# 12-UWB-Power.net
KiCad netlist of a schematic drawn in Altium Designer
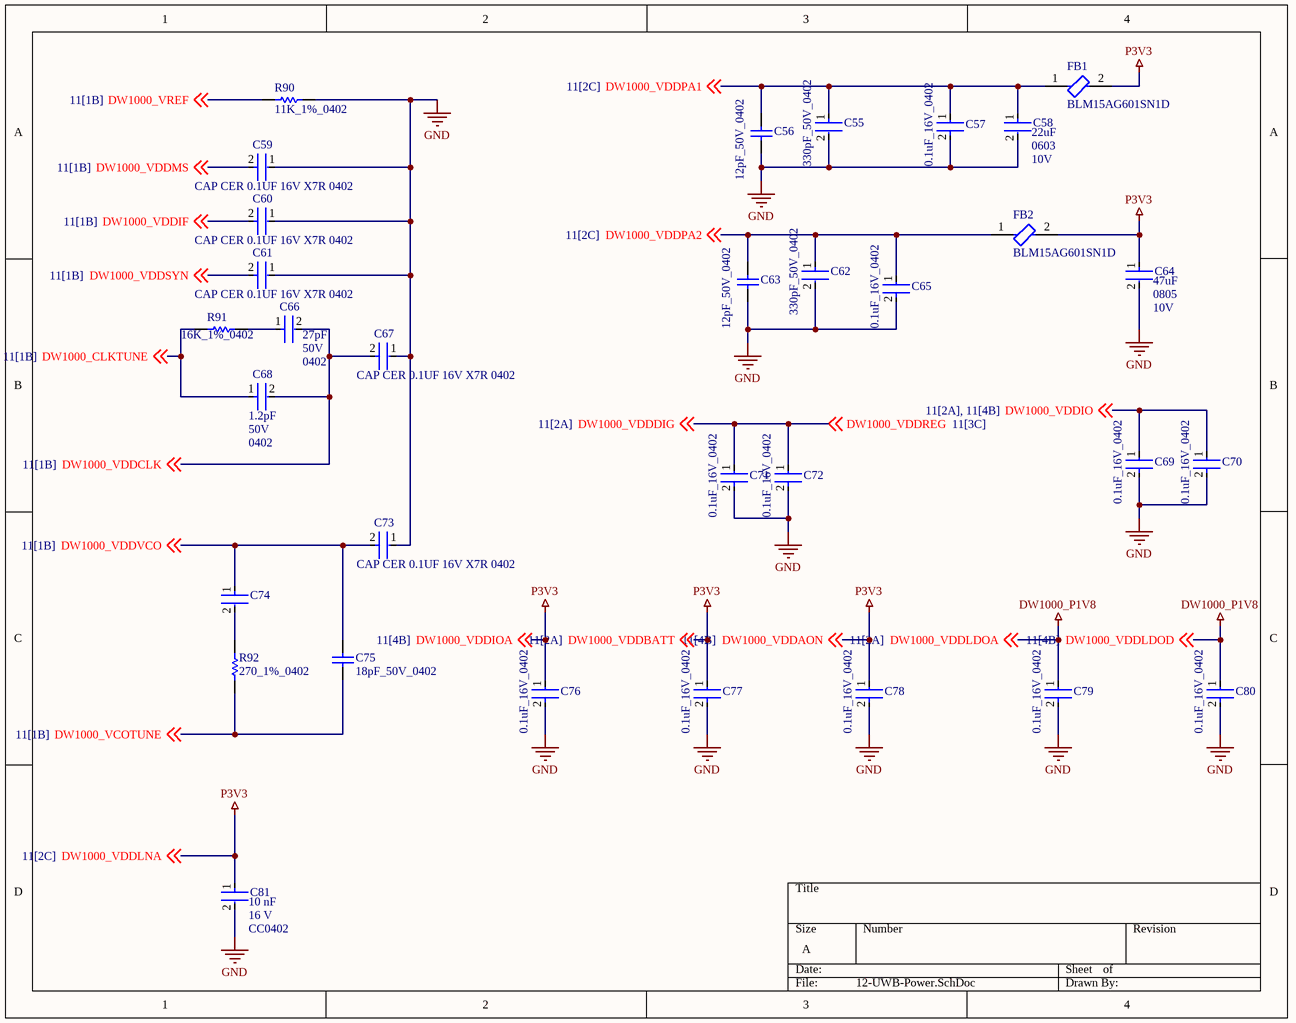
[diagram p0: 12-UWB-Power.SchDoc]

(export (version "E")
  (design (tool "Eeschema 10.0.6"))
  (components
    (comp (ref "C55")
      (value "330pF_50V_0402")
      (footprint "FP-GRM155-0_05-MFG")
      (description "Chip Multilayer Ceramic Capacitors for General Purpose, 0402, 330pF, C0G, 30ppm/°C, 5%, 50V")
      (fields (field (name "TOLERANCE") "5%") (field (name "VOLTAGE") "50V"))
      (libsource (lib "Altium Content Vault") (part "02cd4be3c70576c341d710602a673aa"))
    )
    (comp (ref "C56")
      (value "12pF_50V_0402")
      (footprint "CAPC1005X55X25LL05T05")
      (description "Chip Capacitor, 12 pF, +/- 5%, 50 V, -55 to 125 degC, 0402 (1005 Metric), RoHS, Tape and Reel")
      (fields (field (name "MANUFACTURER") "Yageo") (field (name "TOLERANCE") "±5%"))
      (libsource (lib "Altium Content Vault") (part "CAP-NP-2"))
    )
    (comp (ref "C57")
      (value "0.1uF_16V_0402")
      (footprint "FP-GRM15-MFG")
      (fields
        (field (name "MANUFACTURER PART NUMBER") "GRM155R71C104KA88D")
        (field (name "TOLERANCE") "10%")
        (field (name "OCTOPART") "https://octopart.com/grm155r71c104ka88d-murata-196880")
      )
      (libsource (lib "Altium Content Vault") (part "236180d848d6139a670b325ea6854c9"))
    )
    (comp (ref "C58")
      (value "GRM188R61A226ME15D")
      (footprint "FP-GRM188-0_2-IPC_C")
      (description "Chip Multilayer Ceramic Capacitors for General Purpose, 0603, 22uF, X5R, 15%, 20%, 10V")
      (fields
        (field (name "TOLERANCE") "20%")
        (field (name "CAPACITANCE") "22uF")
        (field (name "VOLTAGE RATING") "10V")
        (field (name "CASE CODE (IMPERIAL)") "0603")
      )
      (libsource (lib "Altium Content Vault") (part "11868f565c42a9108669ba33697ecf6"))
    )
    (comp (ref "C59")
      (value "GRM155R71C104KA88D")
      (footprint "FP-GRM15-MFG")
      (description "CAP CER 0.1UF 16V X7R 0402")
      (fields
        (field (name "TOLERANCE") "10%")
        (field (name "OCTOPART") "https://octopart.com/grm155r71c104ka88d-murata-196880")
        (field (name "DIGIKEY DESCRIPTION") "CAP CER 0.1UF 16V X7R 0402")
      )
      (libsource (lib "Altium Content Vault") (part "236180d848d6139a670b325ea6854c9"))
    )
    (comp (ref "C60")
      (value "GRM155R71C104KA88D")
      (footprint "FP-GRM15-MFG")
      (description "CAP CER 0.1UF 16V X7R 0402")
      (fields
        (field (name "TOLERANCE") "10%")
        (field (name "OCTOPART") "https://octopart.com/grm155r71c104ka88d-murata-196880")
        (field (name "DIGIKEY DESCRIPTION") "CAP CER 0.1UF 16V X7R 0402")
      )
      (libsource (lib "Altium Content Vault") (part "236180d848d6139a670b325ea6854c9"))
    )
    (comp (ref "C61")
      (value "GRM155R71C104KA88D")
      (footprint "FP-GRM15-MFG")
      (description "CAP CER 0.1UF 16V X7R 0402")
      (fields
        (field (name "TOLERANCE") "10%")
        (field (name "OCTOPART") "https://octopart.com/grm155r71c104ka88d-murata-196880")
        (field (name "DIGIKEY DESCRIPTION") "CAP CER 0.1UF 16V X7R 0402")
      )
      (libsource (lib "Altium Content Vault") (part "236180d848d6139a670b325ea6854c9"))
    )
    (comp (ref "C62")
      (value "330pF_50V_0402")
      (footprint "FP-GRM155-0_05-MFG")
      (description "Chip Multilayer Ceramic Capacitors for General Purpose, 0402, 330pF, C0G, 30ppm/°C, 5%, 50V")
      (fields (field (name "TOLERANCE") "5%") (field (name "VOLTAGE") "50V"))
      (libsource (lib "Altium Content Vault") (part "02cd4be3c70576c341d710602a673aa"))
    )
    (comp (ref "C63")
      (value "12pF_50V_0402")
      (footprint "CAPC1005X55X25LL05T05")
      (description "Chip Capacitor, 12 pF, +/- 5%, 50 V, -55 to 125 degC, 0402 (1005 Metric), RoHS, Tape and Reel")
      (fields (field (name "MANUFACTURER") "Yageo") (field (name "TOLERANCE") "±5%"))
      (libsource (lib "Altium Content Vault") (part "CAP-NP-2"))
    )
    (comp (ref "C64")
      (value "GRM21BR61A476ME15L")
      (footprint "FP-GRM21B-0_2-e0_2_0_7-IPC_A")
      (description "Chip Multilayer Ceramic Capacitors for General Purpose, 0805, 47uF, X5R, 15%, 20%, 10V")
      (fields
        (field (name "CAPACITANCE") "47uF")
        (field (name "TOLERANCE") "20%")
        (field (name "CASE CODE (IMPERIAL)") "0805")
        (field (name "VOLTAGE") "10V")
      )
      (libsource (lib "Altium Content Vault") (part "b4654b650e69147ec39a6b967a45e02"))
    )
    (comp (ref "C65")
      (value "0.1uF_16V_0402")
      (footprint "FP-GRM15-MFG")
      (fields
        (field (name "MANUFACTURER PART NUMBER") "GRM155R71C104KA88D")
        (field (name "TOLERANCE") "10%")
        (field (name "OCTOPART") "https://octopart.com/grm155r71c104ka88d-murata-196880")
      )
      (libsource (lib "Altium Content Vault") (part "236180d848d6139a670b325ea6854c9"))
    )
    (comp (ref "C66")
      (value "04025A270JAT2A")
      (footprint "FP-0402-L_1_0_1-W_0_5_0_1-MFG")
      (description "General Purpose Ceramic Capacitor, 0402, 27pF, 5%, C0G, 30ppm/°C, 50V")
      (fields
        (field (name "VOLTAGE RATING") "50V")
        (field (name "VOLTAGE") "50V")
        (field (name "CASE/PACKAGE") "0402")
        (field (name "TOLERANCE") "5%")
        (field (name "CAPACITANCE") "27pF")
      )
      (libsource (lib "Altium Content Vault") (part "b4654b650e69147ec39a6b967a45e02"))
    )
    (comp (ref "C67")
      (value "GRM155R71C104KA88D")
      (footprint "FP-GRM15-MFG")
      (description "CAP CER 0.1UF 16V X7R 0402")
      (fields
        (field (name "TOLERANCE") "10%")
        (field (name "OCTOPART") "https://octopart.com/grm155r71c104ka88d-murata-196880")
        (field (name "DIGIKEY DESCRIPTION") "CAP CER 0.1UF 16V X7R 0402")
      )
      (libsource (lib "Altium Content Vault") (part "236180d848d6139a670b325ea6854c9"))
    )
    (comp (ref "C68")
      (value "GJM1555C1H1R2BB01D")
      (footprint "FP-GJM155-0_05-IPC_B")
      (description "Multi-Layer Ceramic Capacitor 1.2pF C0G  ±0.1pF 0402 Paper T/R")
      (fields
        (field (name "VOLTAGE RATING (DC)") "50V")
        (field (name "CASE CODE (IMPERIAL)") "0402")
        (field (name "VOLTAGE") "50V")
        (field (name "CAPACITANCE") "1.2pF")
      )
      (libsource (lib "Altium Content Vault") (part "02cd4be3c70576c341d710602a673aa"))
    )
    (comp (ref "C69")
      (value "0.1uF_16V_0402")
      (footprint "FP-GRM15-MFG")
      (fields
        (field (name "MANUFACTURER PART NUMBER") "GRM155R71C104KA88D")
        (field (name "TOLERANCE") "10%")
        (field (name "OCTOPART") "https://octopart.com/grm155r71c104ka88d-murata-196880")
      )
      (libsource (lib "Altium Content Vault") (part "236180d848d6139a670b325ea6854c9"))
    )
    (comp (ref "C70")
      (value "0.1uF_16V_0402")
      (footprint "FP-GRM15-MFG")
      (fields
        (field (name "MANUFACTURER PART NUMBER") "GRM155R71C104KA88D")
        (field (name "TOLERANCE") "10%")
        (field (name "OCTOPART") "https://octopart.com/grm155r71c104ka88d-murata-196880")
      )
      (libsource (lib "Altium Content Vault") (part "236180d848d6139a670b325ea6854c9"))
    )
    (comp (ref "C71")
      (value "0.1uF_16V_0402")
      (footprint "FP-GRM15-MFG")
      (fields
        (field (name "MANUFACTURER PART NUMBER") "GRM155R71C104KA88D")
        (field (name "TOLERANCE") "10%")
        (field (name "OCTOPART") "https://octopart.com/grm155r71c104ka88d-murata-196880")
      )
      (libsource (lib "Altium Content Vault") (part "236180d848d6139a670b325ea6854c9"))
    )
    (comp (ref "C72")
      (value "0.1uF_16V_0402")
      (footprint "FP-GRM15-MFG")
      (fields
        (field (name "MANUFACTURER PART NUMBER") "GRM155R71C104KA88D")
        (field (name "TOLERANCE") "10%")
        (field (name "OCTOPART") "https://octopart.com/grm155r71c104ka88d-murata-196880")
      )
      (libsource (lib "Altium Content Vault") (part "236180d848d6139a670b325ea6854c9"))
    )
    (comp (ref "C73")
      (value "GRM155R71C104KA88D")
      (footprint "FP-GRM15-MFG")
      (description "CAP CER 0.1UF 16V X7R 0402")
      (fields
        (field (name "TOLERANCE") "10%")
        (field (name "OCTOPART") "https://octopart.com/grm155r71c104ka88d-murata-196880")
        (field (name "DIGIKEY DESCRIPTION") "CAP CER 0.1UF 16V X7R 0402")
      )
      (libsource (lib "Altium Content Vault") (part "236180d848d6139a670b325ea6854c9"))
    )
    (comp (ref "C74")
      (value "C0402C821K5RACTU")
      (footprint "FP-C0402-BB-MFG")
      (description "CAP CER 820PF 50V 10% X7R 0402")
      (fields (field (name "TOLERANCE") "0.1") (field (name "MANUFACTURER") "Kemet"))
      (libsource (lib "Altium Content Vault") (part "b4654b650e69147ec39a6b967a45e02"))
    )
    (comp (ref "C75")
      (value "18pF_50V_0402")
      (footprint "CAPC1005X55X25NL05T10")
      (fields (field (name "PART NUMBER") "GRM1555C1H180JA01D") (field (name "MANUFACTURER") "Murata"))
      (libsource (lib "Altium Content Vault") (part "CAP"))
    )
    (comp (ref "C76")
      (value "0.1uF_16V_0402")
      (footprint "FP-GRM15-MFG")
      (fields
        (field (name "MANUFACTURER PART NUMBER") "GRM155R71C104KA88D")
        (field (name "TOLERANCE") "10%")
        (field (name "OCTOPART") "https://octopart.com/grm155r71c104ka88d-murata-196880")
      )
      (libsource (lib "Altium Content Vault") (part "236180d848d6139a670b325ea6854c9"))
    )
    (comp (ref "C77")
      (value "0.1uF_16V_0402")
      (footprint "FP-GRM15-MFG")
      (fields
        (field (name "MANUFACTURER PART NUMBER") "GRM155R71C104KA88D")
        (field (name "TOLERANCE") "10%")
        (field (name "OCTOPART") "https://octopart.com/grm155r71c104ka88d-murata-196880")
      )
      (libsource (lib "Altium Content Vault") (part "236180d848d6139a670b325ea6854c9"))
    )
    (comp (ref "C78")
      (value "0.1uF_16V_0402")
      (footprint "FP-GRM15-MFG")
      (fields
        (field (name "MANUFACTURER PART NUMBER") "GRM155R71C104KA88D")
        (field (name "TOLERANCE") "10%")
        (field (name "OCTOPART") "https://octopart.com/grm155r71c104ka88d-murata-196880")
      )
      (libsource (lib "Altium Content Vault") (part "236180d848d6139a670b325ea6854c9"))
    )
    (comp (ref "C79")
      (value "0.1uF_16V_0402")
      (footprint "FP-GRM15-MFG")
      (fields
        (field (name "MANUFACTURER PART NUMBER") "GRM155R71C104KA88D")
        (field (name "TOLERANCE") "10%")
        (field (name "OCTOPART") "https://octopart.com/grm155r71c104ka88d-murata-196880")
      )
      (libsource (lib "Altium Content Vault") (part "236180d848d6139a670b325ea6854c9"))
    )
    (comp (ref "C80")
      (value "0.1uF_16V_0402")
      (footprint "FP-GRM15-MFG")
      (fields
        (field (name "MANUFACTURER PART NUMBER") "GRM155R71C104KA88D")
        (field (name "TOLERANCE") "10%")
        (field (name "OCTOPART") "https://octopart.com/grm155r71c104ka88d-murata-196880")
      )
      (libsource (lib "Altium Content Vault") (part "236180d848d6139a670b325ea6854c9"))
    )
    (comp (ref "C81")
      (value "10 nF")
      (footprint "FP-CC0402-MFG")
      (description "CAP CER 10000PF 16V X7R 0402")
      (fields
        (field (name "MANUFACTURER PART NUMBER") "CC0402KRX7R7BB103")
        (field (name "TOLERANCE") "0.1")
        (field (name "PACKAGE") "CC0402")
        (field (name "VOLTAGE RATING") "16 V")
      )
      (libsource (lib "Altium Content Vault") (part "11868f565c42a9108669ba33697ecf6"))
    )
    (comp (ref "FB1")
      (value "BLM15AG601SN1D")
      (footprint "FP-BLM15-0_05-MFG")
      (description "Chip Ferrite Bead, 0402, 600Ω @ 100MHz, 0.52Ω, 25%, 300mA")
      (fields (field (name "TOLERANCE") "25%"))
      (libsource (lib "Altium Content Vault") (part "5f30dd21d616792df468990f7003faa"))
    )
    (comp (ref "FB2")
      (value "BLM15AG601SN1D")
      (footprint "FP-BLM15-0_05-MFG")
      (description "Chip Ferrite Bead, 0402, 600Ω @ 100MHz, 0.52Ω, 25%, 300mA")
      (fields (field (name "TOLERANCE") "25%"))
      (libsource (lib "Altium Content Vault") (part "5f30dd21d616792df468990f7003faa"))
    )
    (comp (ref "R90")
      (value "11K_1%_0402")
      (footprint "RESC1005X40X25LL05T10")
      (fields (field (name "MANUFACTURER") "Yageo / Phycomp") (field (name "PART NUMBER") "RC0402FR-0711KL"))
      (libsource (lib "Altium Content Vault") (part "RES"))
    )
    (comp (ref "R91")
      (value "16K_1%_0402")
      (footprint "RESC1005X40X25ML05T10")
      (fields (field (name "MANUFACTURER") "Yageo / Phycomp") (field (name "PART NUMBER") "RC0402FR-0716KL"))
      (libsource (lib "Altium Content Vault") (part "RES"))
    )
    (comp (ref "R92")
      (value "270_1%_0402")
      (footprint "RESC1005X40X25ML05T05")
      (fields (field (name "PART NUMBER") "CRCW0402270RFKED") (field (name "MANUFACTURER") "Vishay Dale"))
      (libsource (lib "Altium Content Vault") (part "RES"))
    )
  )
  (nets
    (net (code "1") (name "DW1000_CLKTUNE") (class "Default")
      (node (ref "C68") (pin "1") (pinfunction "1_1") (pintype "passive"))
      (node (ref "R91") (pin "1") (pinfunction "1_1") (pintype "passive"))
    )
    (net (code "2") (name "DW1000_P1V8") (class "Default")
      (node (ref "C79") (pin "1") (pinfunction "1_1") (pintype "passive"))
      (node (ref "C80") (pin "1") (pinfunction "1_1") (pintype "passive"))
    )
    (net (code "3") (name "DW1000_VCOTUNE") (class "Default")
      (node (ref "C75") (pin "1") (pinfunction "1_1") (pintype "passive"))
      (node (ref "R92") (pin "1") (pinfunction "1_1") (pintype "passive"))
    )
    (net (code "4") (name "DW1000_VDDAON") (class "Default")
      (node (ref "C64") (pin "1") (pinfunction "1_1") (pintype "passive"))
      (node (ref "C76") (pin "1") (pinfunction "1_1") (pintype "passive"))
      (node (ref "C77") (pin "1") (pinfunction "1_1") (pintype "passive"))
      (node (ref "C78") (pin "1") (pinfunction "1_1") (pintype "passive"))
      (node (ref "C81") (pin "1") (pinfunction "1_1") (pintype "passive"))
      (node (ref "FB1") (pin "2") (pinfunction "2_2") (pintype "passive"))
      (node (ref "FB2") (pin "2") (pinfunction "2_2") (pintype "passive"))
    )
    (net (code "5") (name "DW1000_VDDCLK") (class "Default")
      (node (ref "C66") (pin "2") (pinfunction "2_2") (pintype "passive"))
      (node (ref "C67") (pin "2") (pinfunction "2_2") (pintype "passive"))
      (node (ref "C68") (pin "2") (pinfunction "2_2") (pintype "passive"))
    )
    (net (code "6") (name "DW1000_VDDDIG") (class "Default")
      (node (ref "C71") (pin "1") (pinfunction "1_1") (pintype "passive"))
      (node (ref "C72") (pin "1") (pinfunction "1_1") (pintype "passive"))
    )
    (net (code "7") (name "DW1000_VDDIF") (class "Default")
      (node (ref "C60") (pin "2") (pinfunction "2_2") (pintype "passive"))
    )
    (net (code "8") (name "DW1000_VDDIO") (class "Default")
      (node (ref "C69") (pin "1") (pinfunction "1_1") (pintype "passive"))
      (node (ref "C70") (pin "1") (pinfunction "1_1") (pintype "passive"))
    )
    (net (code "9") (name "DW1000_VDDMS") (class "Default")
      (node (ref "C59") (pin "2") (pinfunction "2_2") (pintype "passive"))
    )
    (net (code "10") (name "DW1000_VDDPA1") (class "Default")
      (node (ref "C55") (pin "1") (pinfunction "1_1") (pintype "passive"))
      (node (ref "C56") (pin "2") (pinfunction "2_2") (pintype "passive"))
      (node (ref "C57") (pin "1") (pinfunction "1_1") (pintype "passive"))
      (node (ref "C58") (pin "1") (pinfunction "1_1") (pintype "passive"))
      (node (ref "FB1") (pin "1") (pinfunction "1_1") (pintype "passive"))
    )
    (net (code "11") (name "DW1000_VDDPA2") (class "Default")
      (node (ref "C62") (pin "1") (pinfunction "1_1") (pintype "passive"))
      (node (ref "C63") (pin "2") (pinfunction "2_2") (pintype "passive"))
      (node (ref "C65") (pin "1") (pinfunction "1_1") (pintype "passive"))
      (node (ref "FB2") (pin "1") (pinfunction "1_1") (pintype "passive"))
    )
    (net (code "12") (name "DW1000_VDDSYN") (class "Default")
      (node (ref "C61") (pin "2") (pinfunction "2_2") (pintype "passive"))
    )
    (net (code "13") (name "DW1000_VDDVCO") (class "Default")
      (node (ref "C73") (pin "2") (pinfunction "2_2") (pintype "passive"))
      (node (ref "C74") (pin "1") (pinfunction "1_1") (pintype "passive"))
      (node (ref "C75") (pin "2") (pinfunction "2_2") (pintype "passive"))
    )
    (net (code "14") (name "DW1000_VREF") (class "Default")
      (node (ref "R90") (pin "1") (pinfunction "1_1") (pintype "passive"))
    )
    (net (code "15") (name "GND") (class "Default")
      (node (ref "C55") (pin "2") (pinfunction "2_2") (pintype "passive"))
      (node (ref "C56") (pin "1") (pinfunction "1_1") (pintype "passive"))
      (node (ref "C57") (pin "2") (pinfunction "2_2") (pintype "passive"))
      (node (ref "C58") (pin "2") (pinfunction "2_2") (pintype "passive"))
      (node (ref "C59") (pin "1") (pinfunction "1_1") (pintype "passive"))
      (node (ref "C60") (pin "1") (pinfunction "1_1") (pintype "passive"))
      (node (ref "C61") (pin "1") (pinfunction "1_1") (pintype "passive"))
      (node (ref "C62") (pin "2") (pinfunction "2_2") (pintype "passive"))
      (node (ref "C63") (pin "1") (pinfunction "1_1") (pintype "passive"))
      (node (ref "C64") (pin "2") (pinfunction "2_2") (pintype "passive"))
      (node (ref "C65") (pin "2") (pinfunction "2_2") (pintype "passive"))
      (node (ref "C67") (pin "1") (pinfunction "1_1") (pintype "passive"))
      (node (ref "C69") (pin "2") (pinfunction "2_2") (pintype "passive"))
      (node (ref "C70") (pin "2") (pinfunction "2_2") (pintype "passive"))
      (node (ref "C71") (pin "2") (pinfunction "2_2") (pintype "passive"))
      (node (ref "C72") (pin "2") (pinfunction "2_2") (pintype "passive"))
      (node (ref "C73") (pin "1") (pinfunction "1_1") (pintype "passive"))
      (node (ref "C76") (pin "2") (pinfunction "2_2") (pintype "passive"))
      (node (ref "C77") (pin "2") (pinfunction "2_2") (pintype "passive"))
      (node (ref "C78") (pin "2") (pinfunction "2_2") (pintype "passive"))
      (node (ref "C79") (pin "2") (pinfunction "2_2") (pintype "passive"))
      (node (ref "C80") (pin "2") (pinfunction "2_2") (pintype "passive"))
      (node (ref "C81") (pin "2") (pinfunction "2_2") (pintype "passive"))
      (node (ref "R90") (pin "2") (pinfunction "2_2") (pintype "passive"))
    )
    (net (code "16") (name "Net-(C66-Pad1)") (class "Default")
      (node (ref "C66") (pin "1") (pinfunction "1_1") (pintype "passive"))
      (node (ref "R91") (pin "2") (pinfunction "2_2") (pintype "passive"))
    )
    (net (code "17") (name "Net-(C74-Pad2)") (class "Default")
      (node (ref "C74") (pin "2") (pinfunction "2_2") (pintype "passive"))
      (node (ref "R92") (pin "2") (pinfunction "2_2") (pintype "passive"))
    )
  )
)
